# control.net
KiCad netlist of a schematic drawn in EAGLE
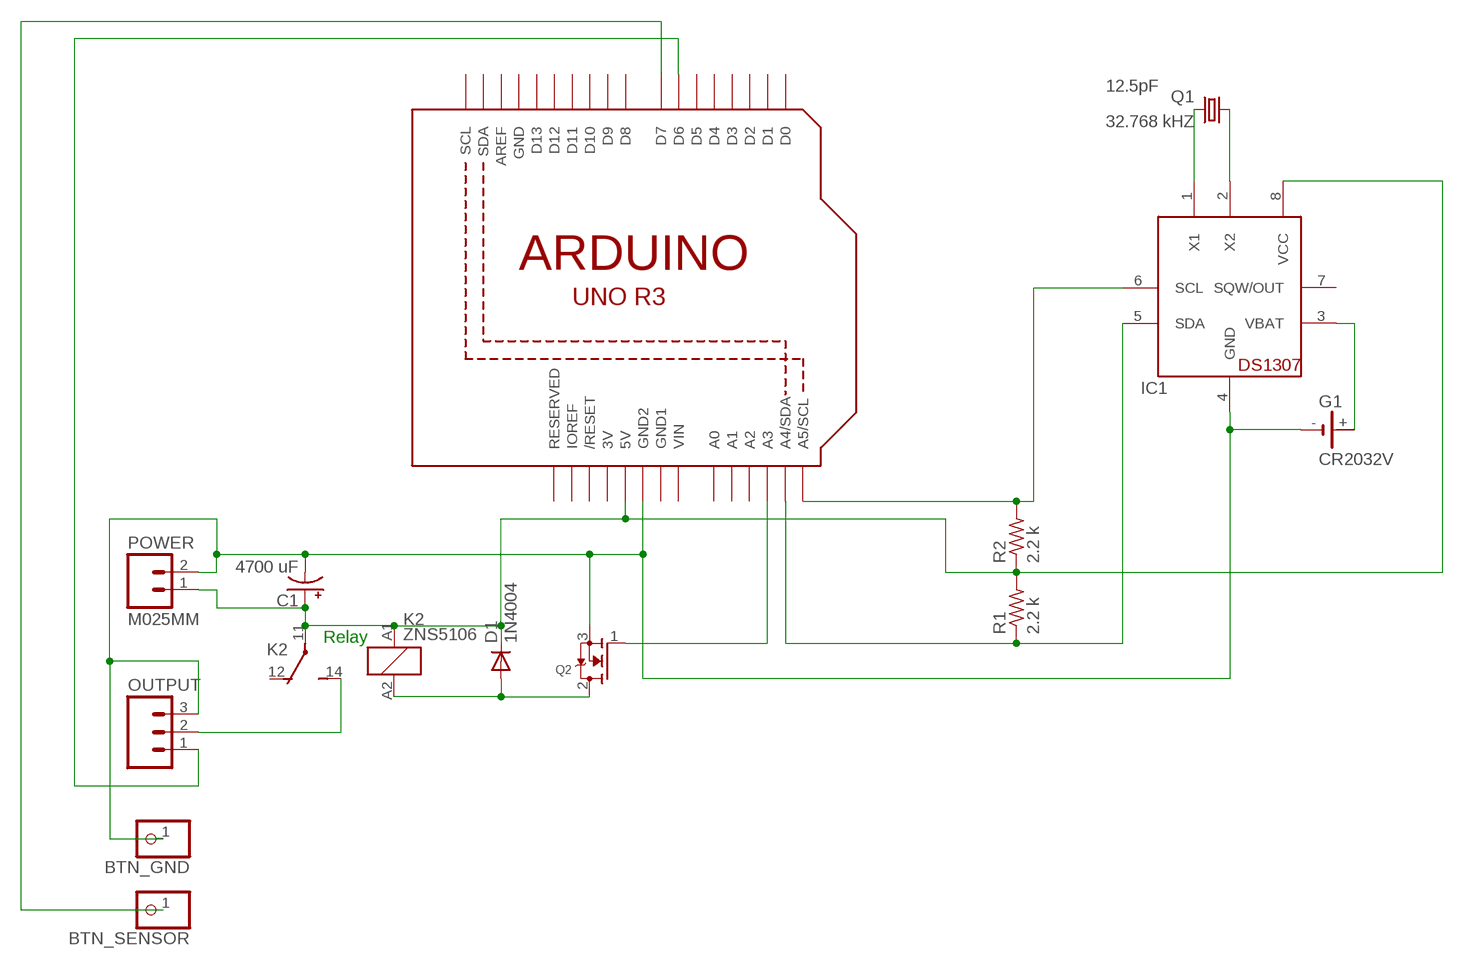
[diagram p0: schematic, sheet 1]

(export (version "E")
  (design (tool "Eeschema 10.0.6"))
  (components
    (comp (ref "BTN_GND")
      (value "PINHD-1X1CB")
      (footprint "eagle-import:1X01-CLEANBIG")
      (libsource (lib "eagle-import") (part "PINHD-1X1CB"))
    )
    (comp (ref "BTN_SENSOR")
      (value "PINHD-1X1CB")
      (footprint "eagle-import:1X01-CLEANBIG")
      (libsource (lib "eagle-import") (part "PINHD-1X1CB"))
    )
    (comp (ref "C1")
      (value "4700 uF")
      (footprint "eagle-import:E5-10,5")
      (libsource (lib "eagle-import") (part "CPOL-USE5-10.5"))
    )
    (comp (ref "D1")
      (value "1N4004")
      (footprint "eagle-import:DO41-10")
      (libsource (lib "eagle-import") (part "1N4004"))
    )
    (comp (ref "G1")
      (value "CR2032V")
      (footprint "eagle-import:CR2032V")
      (libsource (lib "eagle-import") (part "CR2032V"))
    )
    (comp (ref "IC1")
      (value "DS1307")
      (footprint "eagle-import:DIL08")
      (libsource (lib "eagle-import") (part "DS1307"))
    )
    (comp (ref "K2")
      (value "ZNS5106")
      (footprint "eagle-import:ZN5")
      (libsource (lib "eagle-import") (part "ZNS5106"))
    )
    (comp (ref "OUTPUT")
      (value "M03-SCREW-5MM")
      (footprint "eagle-import:SCREWTERMINAL-5MM-3")
      (libsource (lib "eagle-import") (part "M03-SCREW-5MM"))
    )
    (comp (ref "POWER")
      (value "M025MM")
      (footprint "eagle-import:SCREWTERMINAL-5MM-2")
      (libsource (lib "eagle-import") (part "M025MM"))
    )
    (comp (ref "Q1")
      (value "32.768 kHZ")
      (footprint "eagle-import:TC38H")
      (fields (field (name "C") "12.5pF"))
      (libsource (lib "eagle-import") (part "CRYSTALTC38H"))
    )
    (comp (ref "Q2")
      (value "MOSFET-NGDS_TO220V")
      (footprint "eagle-import:TO220V")
      (libsource (lib "eagle-import") (part "MOSFET-NGDS_TO220V"))
    )
    (comp (ref "R1")
      (value "2.2 k")
      (footprint "eagle-import:0207_10")
      (libsource (lib "eagle-import") (part "R-US_0207/10"))
    )
    (comp (ref "R2")
      (value "2.2 k")
      (footprint "eagle-import:0207_10")
      (libsource (lib "eagle-import") (part "R-US_0207/10"))
    )
    (comp (ref "U1")
      (value "ARDUINOR3-BPLACE")
      (footprint "eagle-import:ARDUINOR3-BPLACE")
      (libsource (lib "eagle-import") (part "ARDUINOR3-BPLACE"))
    )
  )
  (nets
    (net (code "1") (name "/3V") (class "Default")
      (node (ref "U1") (pin "3V") (pinfunction "3V_3V") (pintype "power_in"))
    )
    (net (code "2") (name "/GND") (class "Default")
      (node (ref "U1") (pin "GND") (pinfunction "GND_GND") (pintype "power_in"))
    )
    (net (code "3") (name "/GND1") (class "Default")
      (node (ref "U1") (pin "GND1") (pinfunction "GND1_GND1") (pintype "power_in"))
    )
    (net (code "4") (name "/VIN") (class "Default")
      (node (ref "U1") (pin "VIN") (pinfunction "VIN_VIN") (pintype "power_in"))
    )
    (net (code "5") (name "Net-(BTN_SENSOR-Pad1)") (class "Default")
      (node (ref "BTN_SENSOR") (pin "1") (pinfunction "1_1") (pintype "passive"))
      (node (ref "U1") (pin "D7") (pinfunction "D7_D7") (pintype "bidirectional"))
    )
    (net (code "6") (name "Net-(IC1-GND)") (class "Default")
      (node (ref "BTN_GND") (pin "1") (pinfunction "1_1") (pintype "passive"))
      (node (ref "C1") (pin "-") (pinfunction "-_-") (pintype "passive"))
      (node (ref "G1") (pin "-") (pinfunction "-_-") (pintype "passive"))
      (node (ref "IC1") (pin "4") (pinfunction "GND_4") (pintype "power_in"))
      (node (ref "OUTPUT") (pin "3") (pinfunction "3_3") (pintype "passive"))
      (node (ref "POWER") (pin "2") (pinfunction "2_2") (pintype "passive"))
      (node (ref "Q2") (pin "3") (pinfunction "S_3") (pintype "bidirectional"))
      (node (ref "U1") (pin "GND2") (pinfunction "GND2_GND2") (pintype "power_in"))
    )
    (net (code "7") (name "Net-(IC1-SCL)") (class "Default")
      (node (ref "IC1") (pin "6") (pinfunction "SCL_6") (pintype "bidirectional"))
      (node (ref "R2") (pin "2") (pinfunction "2_2") (pintype "passive"))
      (node (ref "U1") (pin "A5") (pinfunction "A5/SCL_A5") (pintype "bidirectional"))
    )
    (net (code "8") (name "Net-(IC1-SDA)") (class "Default")
      (node (ref "IC1") (pin "5") (pinfunction "SDA_5") (pintype "bidirectional"))
      (node (ref "R1") (pin "1") (pinfunction "1_1") (pintype "passive"))
      (node (ref "U1") (pin "A4") (pinfunction "A4/SDA_A4") (pintype "bidirectional"))
    )
    (net (code "9") (name "Net-(IC1-VBAT)") (class "Default")
      (node (ref "G1") (pin "+") (pinfunction "+_+") (pintype "passive"))
      (node (ref "IC1") (pin "3") (pinfunction "VBAT_3") (pintype "power_in"))
    )
    (net (code "10") (name "Net-(IC1-VCC)") (class "Default")
      (node (ref "C1") (pin "+") (pinfunction "+_+") (pintype "passive"))
      (node (ref "D1") (pin "C") (pinfunction "C_C") (pintype "passive"))
      (node (ref "IC1") (pin "8") (pinfunction "VCC_8") (pintype "power_in"))
      (node (ref "K2") (pin "11") (pinfunction "P_11") (pintype "passive"))
      (node (ref "K2") (pin "A1") (pinfunction "1_A1") (pintype "passive"))
      (node (ref "POWER") (pin "1") (pinfunction "1_1") (pintype "passive"))
      (node (ref "R1") (pin "2") (pinfunction "2_2") (pintype "passive"))
      (node (ref "R2") (pin "1") (pinfunction "1_1") (pintype "passive"))
      (node (ref "U1") (pin "5V") (pinfunction "5V_5V") (pintype "power_in"))
    )
    (net (code "11") (name "Net-(IC1-X1)") (class "Default")
      (node (ref "IC1") (pin "1") (pinfunction "X1_1") (pintype "passive"))
      (node (ref "Q1") (pin "2") (pinfunction "2_2") (pintype "passive"))
    )
    (net (code "12") (name "Net-(IC1-X2)") (class "Default")
      (node (ref "IC1") (pin "2") (pinfunction "X2_2") (pintype "passive"))
      (node (ref "Q1") (pin "1") (pinfunction "1_1") (pintype "passive"))
    )
    (net (code "13") (name "Net-(K2A-2)") (class "Default")
      (node (ref "D1") (pin "A") (pinfunction "A_A") (pintype "passive"))
      (node (ref "K2") (pin "A2") (pinfunction "2_A2") (pintype "passive"))
      (node (ref "Q2") (pin "2") (pinfunction "D_2") (pintype "bidirectional"))
    )
    (net (code "14") (name "Net-(K2B-S)") (class "Default")
      (node (ref "K2") (pin "14") (pinfunction "S_14") (pintype "passive"))
      (node (ref "OUTPUT") (pin "2") (pinfunction "2_2") (pintype "passive"))
    )
    (net (code "15") (name "Net-(OUTPUT-Pad1)") (class "Default")
      (node (ref "OUTPUT") (pin "1") (pinfunction "1_1") (pintype "passive"))
      (node (ref "U1") (pin "D6") (pinfunction "D6_D6") (pintype "bidirectional"))
    )
    (net (code "16") (name "Net-(Q2-G)") (class "Default")
      (node (ref "Q2") (pin "1") (pinfunction "G_1") (pintype "bidirectional"))
      (node (ref "U1") (pin "A3") (pinfunction "A3_A3") (pintype "bidirectional"))
    )
    (net (code "17") (name "unconnected-(IC1-SQW{slash}OUT-Pad7)") (class "Default")
      (node (ref "IC1") (pin "7") (pinfunction "SQW/OUT_7") (pintype "bidirectional"))
    )
    (net (code "18") (name "unconnected-(K2B-O-Pad12)") (class "Default")
      (node (ref "K2") (pin "12") (pinfunction "O_12") (pintype "passive"))
    )
    (net (code "19") (name "unconnected-(U1-PadA0)") (class "Default")
      (node (ref "U1") (pin "A0") (pinfunction "A0_A0") (pintype "bidirectional"))
    )
    (net (code "20") (name "unconnected-(U1-PadA1)") (class "Default")
      (node (ref "U1") (pin "A1") (pinfunction "A1_A1") (pintype "bidirectional"))
    )
    (net (code "21") (name "unconnected-(U1-PadA2)") (class "Default")
      (node (ref "U1") (pin "A2") (pinfunction "A2_A2") (pintype "bidirectional"))
    )
    (net (code "22") (name "unconnected-(U1-PadAREF)") (class "Default")
      (node (ref "U1") (pin "AREF") (pinfunction "AREF_AREF") (pintype "bidirectional"))
    )
    (net (code "23") (name "unconnected-(U1-PadD0)") (class "Default")
      (node (ref "U1") (pin "D0") (pinfunction "D0_D0") (pintype "bidirectional"))
    )
    (net (code "24") (name "unconnected-(U1-PadD1)") (class "Default")
      (node (ref "U1") (pin "D1") (pinfunction "D1_D1") (pintype "bidirectional"))
    )
    (net (code "25") (name "unconnected-(U1-PadD2)") (class "Default")
      (node (ref "U1") (pin "D2") (pinfunction "D2_D2") (pintype "bidirectional"))
    )
    (net (code "26") (name "unconnected-(U1-PadD3)") (class "Default")
      (node (ref "U1") (pin "D3") (pinfunction "D3_D3") (pintype "bidirectional"))
    )
    (net (code "27") (name "unconnected-(U1-PadD4)") (class "Default")
      (node (ref "U1") (pin "D4") (pinfunction "D4_D4") (pintype "bidirectional"))
    )
    (net (code "28") (name "unconnected-(U1-PadD5)") (class "Default")
      (node (ref "U1") (pin "D5") (pinfunction "D5_D5") (pintype "bidirectional"))
    )
    (net (code "29") (name "unconnected-(U1-PadD8)") (class "Default")
      (node (ref "U1") (pin "D8") (pinfunction "D8_D8") (pintype "bidirectional"))
    )
    (net (code "30") (name "unconnected-(U1-PadD9)") (class "Default")
      (node (ref "U1") (pin "D9") (pinfunction "D9_D9") (pintype "bidirectional"))
    )
    (net (code "31") (name "unconnected-(U1-PadD10)") (class "Default")
      (node (ref "U1") (pin "D10") (pinfunction "D10_D10") (pintype "bidirectional"))
    )
    (net (code "32") (name "unconnected-(U1-PadD11)") (class "Default")
      (node (ref "U1") (pin "D11") (pinfunction "D11_D11") (pintype "bidirectional"))
    )
    (net (code "33") (name "unconnected-(U1-PadD12)") (class "Default")
      (node (ref "U1") (pin "D12") (pinfunction "D12_D12") (pintype "bidirectional"))
    )
    (net (code "34") (name "unconnected-(U1-PadD13)") (class "Default")
      (node (ref "U1") (pin "D13") (pinfunction "D13_D13") (pintype "bidirectional"))
    )
    (net (code "35") (name "unconnected-(U1-PadIOREF)") (class "Default")
      (node (ref "U1") (pin "IOREF") (pinfunction "IOREF_IOREF") (pintype "output"))
    )
    (net (code "36") (name "unconnected-(U1-PadRESERVED)") (class "Default")
      (node (ref "U1") (pin "RESERVED") (pinfunction "RESERVED_RESERVED") (pintype "no_connect"))
    )
    (net (code "37") (name "unconnected-(U1-PadSCL)") (class "Default")
      (node (ref "U1") (pin "SCL") (pinfunction "SCL_SCL") (pintype "bidirectional"))
    )
    (net (code "38") (name "unconnected-(U1-PadSDA)") (class "Default")
      (node (ref "U1") (pin "SDA") (pinfunction "SDA_SDA") (pintype "bidirectional"))
    )
    (net (code "39") (name "unconnected-(U1-{slash}RESET-PadRESET)") (class "Default")
      (node (ref "U1") (pin "RESET") (pinfunction "/RESET_RESET") (pintype "bidirectional"))
    )
  )
)
